# LoRa.net
KiCad netlist of a schematic drawn in Altium Designer
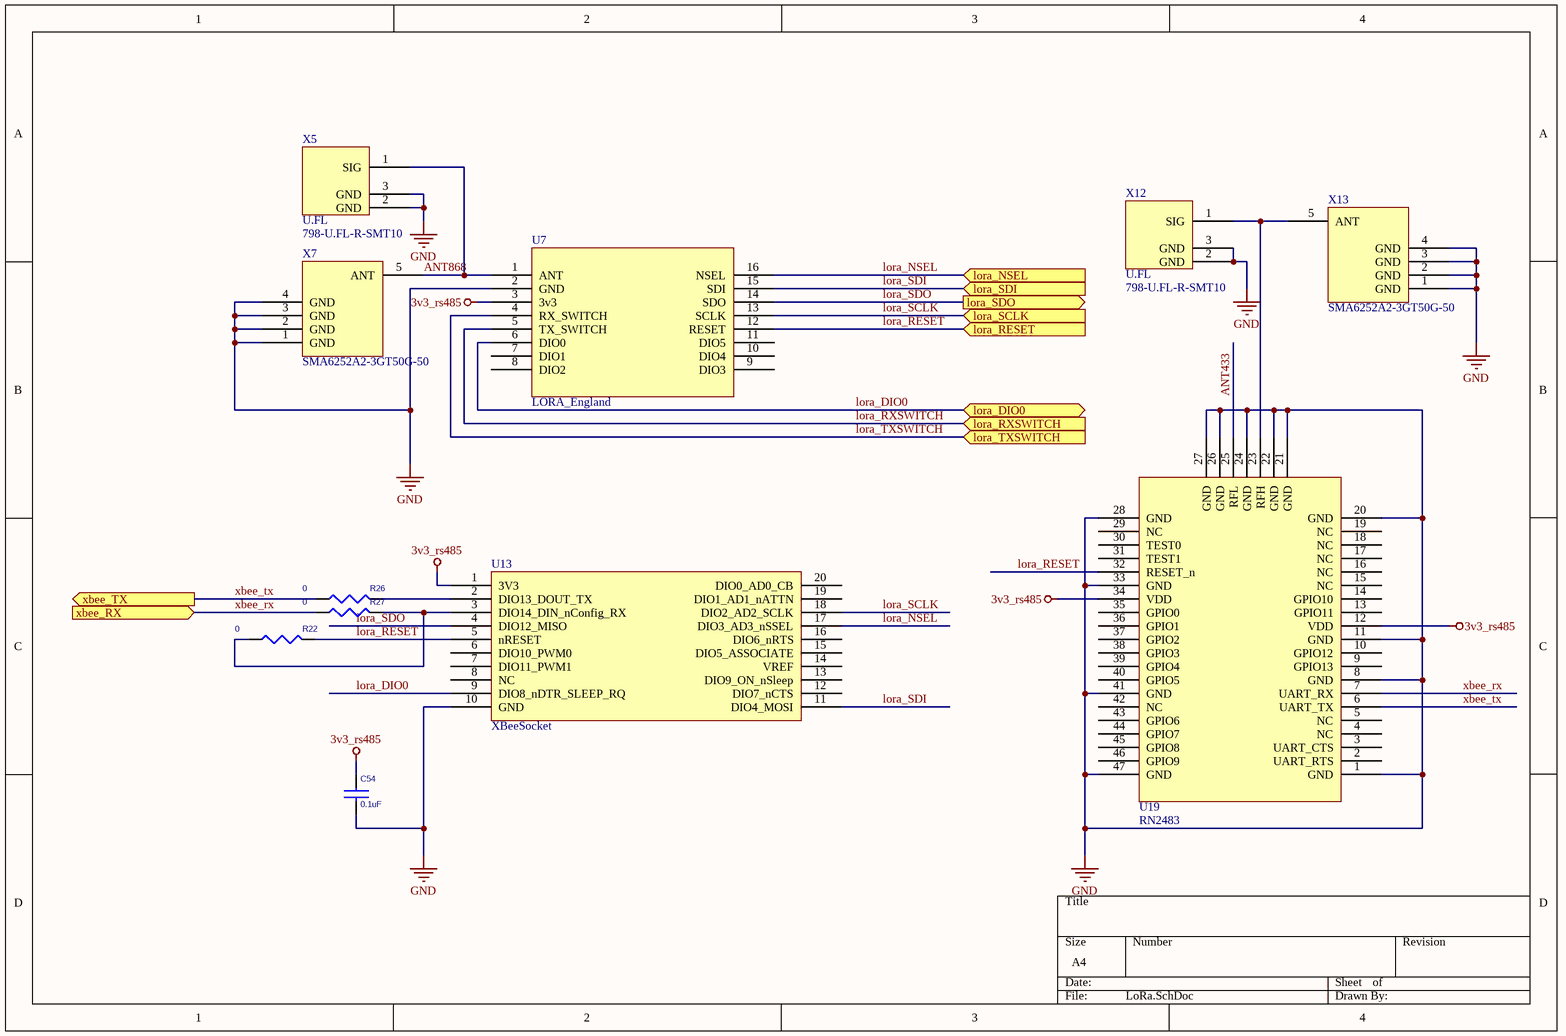
[diagram p0: LoRa.SchDoc]

(export (version "E")
  (design (tool "Eeschema 10.0.6"))
  (components
    (comp (ref "C54")
      (value "0.1uF")
      (footprint "CAPC2012X09M")
      (description "CAP CER 0.1UF 25V 10% X7R 0805")
      (libsource (lib "Capacitors") (part "CAP_SMD_0.1UF_10%"))
    )
    (comp (ref "R22")
      (value "0")
      (footprint "RESC2013X06M")
      (description "RES 0.0 OHM 1/8W JUMP 0805 SMD")
      (libsource (lib "Resistors") (part "RES_SMD_0"))
    )
    (comp (ref "R26")
      (value "0")
      (footprint "RESC2013X06M")
      (description "RES 0.0 OHM 1/8W JUMP 0805 SMD")
      (libsource (lib "Resistors") (part "RES_SMD_0"))
    )
    (comp (ref "R27")
      (value "0")
      (footprint "RESC2013X06M")
      (description "RES 0.0 OHM 1/8W JUMP 0805 SMD")
      (libsource (lib "Resistors") (part "RES_SMD_0"))
    )
    (comp (ref "U7")
      (value "LORA_England")
      (footprint "DIP16")
      (libsource (lib "TruthEar") (part "LORA_MODULE_E"))
    )
    (comp (ref "U13")
      (value "XBeeSocket")
      (footprint "DIP20_XBEE")
      (libsource (lib "TruthEar") (part "XBEE_Module"))
    )
    (comp (ref "U19") (value "RN2483") (footprint "RN2483") (libsource (lib "TruthEar") (part "RN2383")))
    (comp (ref "X5")
      (value "U.FL")
      (footprint "U.FL")
      (fields (field (name "SUPPLIER PART NUMBER 1") "798-U.FL-R-SMT10"))
      (libsource (lib "Connectors") (part "U.FL"))
    )
    (comp (ref "X7")
      (value "SMA6252A2-3GT50G-50")
      (footprint "SMA6252A2-3GT50G-50")
      (libsource (lib "") (part "SMA_CONN_1"))
    )
    (comp (ref "X12")
      (value "U.FL")
      (footprint "U.FL")
      (fields (field (name "SUPPLIER PART NUMBER 1") "798-U.FL-R-SMT10"))
      (libsource (lib "Connectors") (part "U.FL"))
    )
    (comp (ref "X13")
      (value "SMA6252A2-3GT50G-50")
      (footprint "SMA6252A2-3GT50G-50")
      (libsource (lib "Connectors") (part "SMA_CONN"))
    )
  )
  (nets
    (net (code "1") (name "/ANT433") (class "Default")
      (node (ref "U19") (pin "25") (pinfunction "RFL_25") (pintype "passive"))
    )
    (net (code "2") (name "/ANT868") (class "Default")
      (node (ref "U7") (pin "1") (pinfunction "ANT_1") (pintype "passive"))
      (node (ref "X5") (pin "1") (pinfunction "SIG_1") (pintype "passive"))
      (node (ref "X7") (pin "5") (pinfunction "ANT_5") (pintype "passive"))
    )
    (net (code "3") (name "/lora_DIO0") (class "Default")
      (node (ref "U13") (pin "9") (pinfunction "DIO8_nDTR_SLEEP_RQ_9") (pintype "passive"))
      (node (ref "U7") (pin "6") (pinfunction "DIO0_6") (pintype "passive"))
    )
    (net (code "4") (name "/lora_NSEL") (class "Default")
      (node (ref "U13") (pin "17") (pinfunction "DIO3_AD3_nSSEL_17") (pintype "passive"))
      (node (ref "U7") (pin "16") (pinfunction "NSEL_16") (pintype "passive"))
    )
    (net (code "5") (name "/lora_RESET") (class "Default")
      (node (ref "R22") (pin "2") (pinfunction "2_2") (pintype "passive"))
      (node (ref "U13") (pin "5") (pinfunction "nRESET_5") (pintype "passive"))
      (node (ref "U19") (pin "32") (pinfunction "RESET_n_32") (pintype "passive"))
      (node (ref "U7") (pin "12") (pinfunction "RESET_12") (pintype "passive"))
    )
    (net (code "6") (name "/lora_RXSWITCH") (class "Default")
      (node (ref "U7") (pin "5") (pinfunction "TX_SWITCH_5") (pintype "passive"))
    )
    (net (code "7") (name "/lora_SCLK") (class "Default")
      (node (ref "U13") (pin "18") (pinfunction "DIO2_AD2_SCLK_18") (pintype "passive"))
      (node (ref "U7") (pin "13") (pinfunction "SCLK_13") (pintype "passive"))
    )
    (net (code "8") (name "/lora_SDI") (class "Default")
      (node (ref "U13") (pin "11") (pinfunction "DIO4_MOSI_11") (pintype "passive"))
      (node (ref "U7") (pin "15") (pinfunction "SDI_15") (pintype "passive"))
    )
    (net (code "9") (name "/lora_SDO") (class "Default")
      (node (ref "U13") (pin "4") (pinfunction "DIO12_MISO_4") (pintype "passive"))
      (node (ref "U7") (pin "14") (pinfunction "SDO_14") (pintype "passive"))
    )
    (net (code "10") (name "/lora_TXSWITCH") (class "Default")
      (node (ref "U7") (pin "4") (pinfunction "RX_SWITCH_4") (pintype "passive"))
    )
    (net (code "11") (name "/xbee_rx") (class "Default")
      (node (ref "R27") (pin "1") (pinfunction "1_1") (pintype "passive"))
      (node (ref "U19") (pin "7") (pinfunction "UART_RX_7") (pintype "passive"))
    )
    (net (code "12") (name "/xbee_tx") (class "Default")
      (node (ref "R26") (pin "1") (pinfunction "1_1") (pintype "passive"))
      (node (ref "U19") (pin "6") (pinfunction "UART_TX_6") (pintype "passive"))
    )
    (net (code "13") (name "3v3_rs485") (class "Default")
      (node (ref "C54") (pin "1") (pinfunction "1_1") (pintype "passive"))
      (node (ref "U13") (pin "1") (pinfunction "3V3_1") (pintype "passive"))
      (node (ref "U19") (pin "12") (pinfunction "VDD_12") (pintype "passive"))
      (node (ref "U19") (pin "34") (pinfunction "VDD_34") (pintype "passive"))
      (node (ref "U7") (pin "3") (pinfunction "3v3_3") (pintype "passive"))
    )
    (net (code "14") (name "GND") (class "Default")
      (node (ref "C54") (pin "2") (pinfunction "2_2") (pintype "passive"))
      (node (ref "U13") (pin "10") (pinfunction "GND_10") (pintype "passive"))
      (node (ref "U19") (pin "1") (pinfunction "GND_1") (pintype "passive"))
      (node (ref "U19") (pin "11") (pinfunction "GND_11") (pintype "passive"))
      (node (ref "U19") (pin "20") (pinfunction "GND_20") (pintype "passive"))
      (node (ref "U19") (pin "21") (pinfunction "GND_21") (pintype "passive"))
      (node (ref "U19") (pin "22") (pinfunction "GND_22") (pintype "passive"))
      (node (ref "U19") (pin "24") (pinfunction "GND_24") (pintype "passive"))
      (node (ref "U19") (pin "26") (pinfunction "GND_26") (pintype "passive"))
      (node (ref "U19") (pin "27") (pinfunction "GND_27") (pintype "passive"))
      (node (ref "U19") (pin "28") (pinfunction "GND_28") (pintype "passive"))
      (node (ref "U19") (pin "33") (pinfunction "GND_33") (pintype "passive"))
      (node (ref "U19") (pin "41") (pinfunction "GND_41") (pintype "passive"))
      (node (ref "U19") (pin "47") (pinfunction "GND_47") (pintype "passive"))
      (node (ref "U19") (pin "8") (pinfunction "GND_8") (pintype "passive"))
      (node (ref "U7") (pin "2") (pinfunction "GND_2") (pintype "passive"))
      (node (ref "X12") (pin "2") (pinfunction "GND_2") (pintype "passive"))
      (node (ref "X12") (pin "3") (pinfunction "GND_3") (pintype "passive"))
      (node (ref "X13") (pin "1") (pinfunction "GND_1") (pintype "passive"))
      (node (ref "X13") (pin "2") (pinfunction "GND_2") (pintype "passive"))
      (node (ref "X13") (pin "3") (pinfunction "GND_3") (pintype "passive"))
      (node (ref "X13") (pin "4") (pinfunction "GND_4") (pintype "passive"))
      (node (ref "X5") (pin "2") (pinfunction "GND_2") (pintype "passive"))
      (node (ref "X5") (pin "3") (pinfunction "GND_3") (pintype "passive"))
      (node (ref "X7") (pin "1") (pinfunction "GND_1") (pintype "passive"))
      (node (ref "X7") (pin "2") (pinfunction "GND_2") (pintype "passive"))
      (node (ref "X7") (pin "3") (pinfunction "GND_3") (pintype "passive"))
      (node (ref "X7") (pin "4") (pinfunction "GND_4") (pintype "passive"))
    )
    (net (code "15") (name "Net-(U13-DIO13_DOUT_TX)") (class "Default")
      (node (ref "R26") (pin "2") (pinfunction "2_2") (pintype "passive"))
      (node (ref "U13") (pin "2") (pinfunction "DIO13_DOUT_TX_2") (pintype "passive"))
    )
    (net (code "16") (name "Net-(U13-DIO14_DIN_nConfig_RX)") (class "Default")
      (node (ref "R22") (pin "1") (pinfunction "1_1") (pintype "passive"))
      (node (ref "R27") (pin "2") (pinfunction "2_2") (pintype "passive"))
      (node (ref "U13") (pin "3") (pinfunction "DIO14_DIN_nConfig_RX_3") (pintype "passive"))
    )
    (net (code "17") (name "Net-(U19-RFH)") (class "Default")
      (node (ref "U19") (pin "23") (pinfunction "RFH_23") (pintype "passive"))
      (node (ref "X12") (pin "1") (pinfunction "SIG_1") (pintype "passive"))
      (node (ref "X13") (pin "5") (pinfunction "ANT_5") (pintype "passive"))
    )
    (net (code "18") (name "unconnected-(U7-DIO1-Pad7)") (class "Default")
      (node (ref "U7") (pin "7") (pinfunction "DIO1_7") (pintype "passive"))
    )
    (net (code "19") (name "unconnected-(U7-DIO2-Pad8)") (class "Default")
      (node (ref "U7") (pin "8") (pinfunction "DIO2_8") (pintype "passive"))
    )
    (net (code "20") (name "unconnected-(U7-DIO3-Pad9)") (class "Default")
      (node (ref "U7") (pin "9") (pinfunction "DIO3_9") (pintype "passive"))
    )
    (net (code "21") (name "unconnected-(U7-DIO4-Pad10)") (class "Default")
      (node (ref "U7") (pin "10") (pinfunction "DIO4_10") (pintype "passive"))
    )
    (net (code "22") (name "unconnected-(U7-DIO5-Pad11)") (class "Default")
      (node (ref "U7") (pin "11") (pinfunction "DIO5_11") (pintype "passive"))
    )
    (net (code "23") (name "unconnected-(U13-DIO0_AD0_CB-Pad20)") (class "Default")
      (node (ref "U13") (pin "20") (pinfunction "DIO0_AD0_CB_20") (pintype "passive"))
    )
    (net (code "24") (name "unconnected-(U13-DIO1_AD1_nATTN-Pad19)") (class "Default")
      (node (ref "U13") (pin "19") (pinfunction "DIO1_AD1_nATTN_19") (pintype "passive"))
    )
    (net (code "25") (name "unconnected-(U13-DIO5_ASSOCIATE-Pad15)") (class "Default")
      (node (ref "U13") (pin "15") (pinfunction "DIO5_ASSOCIATE_15") (pintype "passive"))
    )
    (net (code "26") (name "unconnected-(U13-DIO6_nRTS-Pad16)") (class "Default")
      (node (ref "U13") (pin "16") (pinfunction "DIO6_nRTS_16") (pintype "passive"))
    )
    (net (code "27") (name "unconnected-(U13-DIO7_nCTS-Pad12)") (class "Default")
      (node (ref "U13") (pin "12") (pinfunction "DIO7_nCTS_12") (pintype "passive"))
    )
    (net (code "28") (name "unconnected-(U13-DIO9_ON_nSleep-Pad13)") (class "Default")
      (node (ref "U13") (pin "13") (pinfunction "DIO9_ON_nSleep_13") (pintype "passive"))
    )
    (net (code "29") (name "unconnected-(U13-DIO10_PWM0-Pad6)") (class "Default")
      (node (ref "U13") (pin "6") (pinfunction "DIO10_PWM0_6") (pintype "passive"))
    )
    (net (code "30") (name "unconnected-(U13-DIO11_PWM1-Pad7)") (class "Default")
      (node (ref "U13") (pin "7") (pinfunction "DIO11_PWM1_7") (pintype "passive"))
    )
    (net (code "31") (name "unconnected-(U13-NC-Pad8)") (class "Default")
      (node (ref "U13") (pin "8") (pinfunction "NC_8") (pintype "passive"))
    )
    (net (code "32") (name "unconnected-(U13-VREF-Pad14)") (class "Default")
      (node (ref "U13") (pin "14") (pinfunction "VREF_14") (pintype "passive"))
    )
    (net (code "33") (name "unconnected-(U19-GPIO0-Pad35)") (class "Default")
      (node (ref "U19") (pin "35") (pinfunction "GPIO0_35") (pintype "passive"))
    )
    (net (code "34") (name "unconnected-(U19-GPIO1-Pad36)") (class "Default")
      (node (ref "U19") (pin "36") (pinfunction "GPIO1_36") (pintype "passive"))
    )
    (net (code "35") (name "unconnected-(U19-GPIO2-Pad37)") (class "Default")
      (node (ref "U19") (pin "37") (pinfunction "GPIO2_37") (pintype "passive"))
    )
    (net (code "36") (name "unconnected-(U19-GPIO3-Pad38)") (class "Default")
      (node (ref "U19") (pin "38") (pinfunction "GPIO3_38") (pintype "passive"))
    )
    (net (code "37") (name "unconnected-(U19-GPIO4-Pad39)") (class "Default")
      (node (ref "U19") (pin "39") (pinfunction "GPIO4_39") (pintype "passive"))
    )
    (net (code "38") (name "unconnected-(U19-GPIO5-Pad40)") (class "Default")
      (node (ref "U19") (pin "40") (pinfunction "GPIO5_40") (pintype "passive"))
    )
    (net (code "39") (name "unconnected-(U19-GPIO6-Pad43)") (class "Default")
      (node (ref "U19") (pin "43") (pinfunction "GPIO6_43") (pintype "passive"))
    )
    (net (code "40") (name "unconnected-(U19-GPIO7-Pad44)") (class "Default")
      (node (ref "U19") (pin "44") (pinfunction "GPIO7_44") (pintype "passive"))
    )
    (net (code "41") (name "unconnected-(U19-GPIO8-Pad45)") (class "Default")
      (node (ref "U19") (pin "45") (pinfunction "GPIO8_45") (pintype "passive"))
    )
    (net (code "42") (name "unconnected-(U19-GPIO9-Pad46)") (class "Default")
      (node (ref "U19") (pin "46") (pinfunction "GPIO9_46") (pintype "passive"))
    )
    (net (code "43") (name "unconnected-(U19-GPIO10-Pad14)") (class "Default")
      (node (ref "U19") (pin "14") (pinfunction "GPIO10_14") (pintype "passive"))
    )
    (net (code "44") (name "unconnected-(U19-GPIO11-Pad13)") (class "Default")
      (node (ref "U19") (pin "13") (pinfunction "GPIO11_13") (pintype "passive"))
    )
    (net (code "45") (name "unconnected-(U19-GPIO12-Pad10)") (class "Default")
      (node (ref "U19") (pin "10") (pinfunction "GPIO12_10") (pintype "passive"))
    )
    (net (code "46") (name "unconnected-(U19-GPIO13-Pad9)") (class "Default")
      (node (ref "U19") (pin "9") (pinfunction "GPIO13_9") (pintype "passive"))
    )
    (net (code "47") (name "unconnected-(U19-NC-Pad4)") (class "Default")
      (node (ref "U19") (pin "4") (pinfunction "NC_4") (pintype "passive"))
    )
    (net (code "48") (name "unconnected-(U19-NC-Pad5)") (class "Default")
      (node (ref "U19") (pin "5") (pinfunction "NC_5") (pintype "passive"))
    )
    (net (code "49") (name "unconnected-(U19-NC-Pad15)") (class "Default")
      (node (ref "U19") (pin "15") (pinfunction "NC_15") (pintype "passive"))
    )
    (net (code "50") (name "unconnected-(U19-NC-Pad16)") (class "Default")
      (node (ref "U19") (pin "16") (pinfunction "NC_16") (pintype "passive"))
    )
    (net (code "51") (name "unconnected-(U19-NC-Pad17)") (class "Default")
      (node (ref "U19") (pin "17") (pinfunction "NC_17") (pintype "passive"))
    )
    (net (code "52") (name "unconnected-(U19-NC-Pad18)") (class "Default")
      (node (ref "U19") (pin "18") (pinfunction "NC_18") (pintype "passive"))
    )
    (net (code "53") (name "unconnected-(U19-NC-Pad19)") (class "Default")
      (node (ref "U19") (pin "19") (pinfunction "NC_19") (pintype "passive"))
    )
    (net (code "54") (name "unconnected-(U19-NC-Pad29)") (class "Default")
      (node (ref "U19") (pin "29") (pinfunction "NC_29") (pintype "passive"))
    )
    (net (code "55") (name "unconnected-(U19-NC-Pad42)") (class "Default")
      (node (ref "U19") (pin "42") (pinfunction "NC_42") (pintype "passive"))
    )
    (net (code "56") (name "unconnected-(U19-TEST0-Pad30)") (class "Default")
      (node (ref "U19") (pin "30") (pinfunction "TEST0_30") (pintype "passive"))
    )
    (net (code "57") (name "unconnected-(U19-TEST1-Pad31)") (class "Default")
      (node (ref "U19") (pin "31") (pinfunction "TEST1_31") (pintype "passive"))
    )
    (net (code "58") (name "unconnected-(U19-UART_CTS-Pad3)") (class "Default")
      (node (ref "U19") (pin "3") (pinfunction "UART_CTS_3") (pintype "passive"))
    )
    (net (code "59") (name "unconnected-(U19-UART_RTS-Pad2)") (class "Default")
      (node (ref "U19") (pin "2") (pinfunction "UART_RTS_2") (pintype "passive"))
    )
  )
)
